# ES.net
KiCad netlist of a schematic drawn in Altium Designer
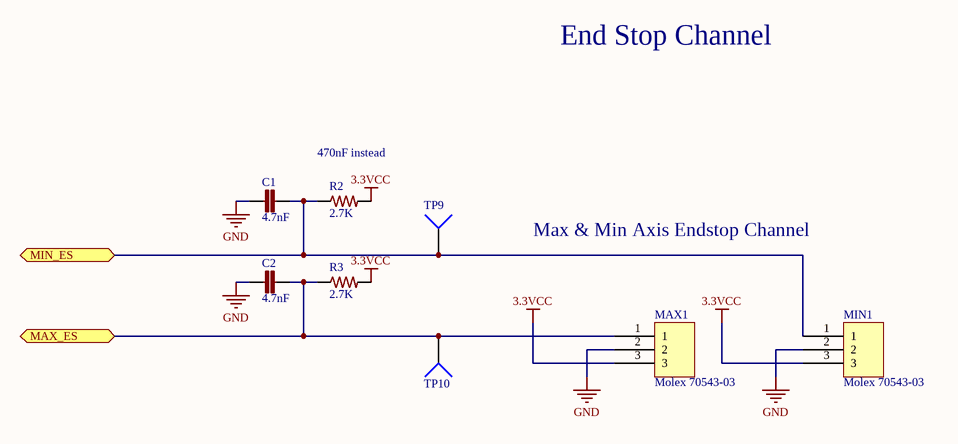
[diagram p0: ES.SchDoc]

(export (version "E")
  (design (tool "Eeschema 10.0.6"))
  (components
    (comp (ref "C1")
      (value "4.7nF")
      (footprint "C0402")
      (description "CAP CER 0402 4.7nF 25V 10% X7R")
      (fields
        (field (name "MANUFACTURERPARTNUMBER") "CC0402KRX7R8BB472")
        (field (name "PUBLISHER") "UltiMachine")
      )
      (libsource (lib "3Delight") (part "CC0402KRX7R8BB472"))
    )
    (comp (ref "C2")
      (value "4.7nF")
      (footprint "C0402")
      (description "CAP CER 0402 4.7nF 25V 10% X7R")
      (fields
        (field (name "MANUFACTURERPARTNUMBER") "CC0402KRX7R8BB472")
        (field (name "PUBLISHER") "UltiMachine")
      )
      (libsource (lib "3Delight") (part "CC0402KRX7R8BB472"))
    )
    (comp (ref "MAX1")
      (value "Molex 70543-03")
      (footprint "70543-03")
      (libsource (lib "RADMBo Schematic Library") (part "Molex Endstop"))
    )
    (comp (ref "MIN1")
      (value "Molex 70543-03")
      (footprint "70543-03")
      (libsource (lib "RADMBo Schematic Library") (part "Molex Endstop"))
    )
    (comp (ref "R2")
      (value "2.7K")
      (footprint "R0402")
      (description "RES SMD 2.7K OHM 5% 1/10W 0402")
      (fields
        (field (name "MANUFACTURERPARTNUMBER") "ERJ-2GEJ272X")
        (field (name "TOLERANCE") "5%")
        (field (name "PUBLISHER") "Adam Vadala-Roth")
      )
      (libsource (lib "Tigershark3D") (part "ERJ-2GEJ272X"))
    )
    (comp (ref "R3")
      (value "2.7K")
      (footprint "R0402")
      (description "RES SMD 2.7K OHM 5% 1/10W 0402")
      (fields
        (field (name "MANUFACTURERPARTNUMBER") "ERJ-2GEJ272X")
        (field (name "TOLERANCE") "5%")
        (field (name "PUBLISHER") "Adam Vadala-Roth")
      )
      (libsource (lib "Tigershark3D") (part "ERJ-2GEJ272X"))
    )
    (comp (ref "TP9")
      (value "TP4")
      (footprint "TP-2")
      (description "Socket")
      (fields (field (name "PUBLISHER") "Altium Limited"))
      (libsource (lib "ZMBo Schematic Library") (part "Socket"))
    )
    (comp (ref "TP10")
      (value "TP4")
      (footprint "TP-2")
      (description "Socket")
      (fields (field (name "PUBLISHER") "Altium Limited"))
      (libsource (lib "ZMBo Schematic Library") (part "Socket"))
    )
  )
  (nets
    (net (code "1") (name "/MAX_ES") (class "Default")
      (node (ref "C2") (pin "2") (pinfunction "2_2") (pintype "passive"))
      (node (ref "MAX1") (pin "1") (pinfunction "1_1") (pintype "passive"))
      (node (ref "R3") (pin "1") (pinfunction "1_1") (pintype "passive"))
      (node (ref "TP10") (pin "1") (pinfunction "1_1") (pintype "passive"))
    )
    (net (code "2") (name "/MIN_ES") (class "Default")
      (node (ref "C1") (pin "2") (pinfunction "2_2") (pintype "passive"))
      (node (ref "MIN1") (pin "1") (pinfunction "1_1") (pintype "passive"))
      (node (ref "R2") (pin "1") (pinfunction "1_1") (pintype "passive"))
      (node (ref "TP9") (pin "1") (pinfunction "1_1") (pintype "passive"))
    )
    (net (code "3") (name "3.3VCC") (class "Default")
      (node (ref "MAX1") (pin "3") (pinfunction "3_3") (pintype "passive"))
      (node (ref "MIN1") (pin "3") (pinfunction "3_3") (pintype "passive"))
      (node (ref "R2") (pin "2") (pinfunction "2_2") (pintype "passive"))
      (node (ref "R3") (pin "2") (pinfunction "2_2") (pintype "passive"))
    )
    (net (code "4") (name "GND") (class "Default")
      (node (ref "C1") (pin "1") (pinfunction "1_1") (pintype "passive"))
      (node (ref "C2") (pin "1") (pinfunction "1_1") (pintype "passive"))
      (node (ref "MAX1") (pin "2") (pinfunction "2_2") (pintype "passive"))
      (node (ref "MIN1") (pin "2") (pinfunction "2_2") (pintype "passive"))
    )
  )
)
